# untitled.net
KiCad netlist of a schematic drawn in EAGLE
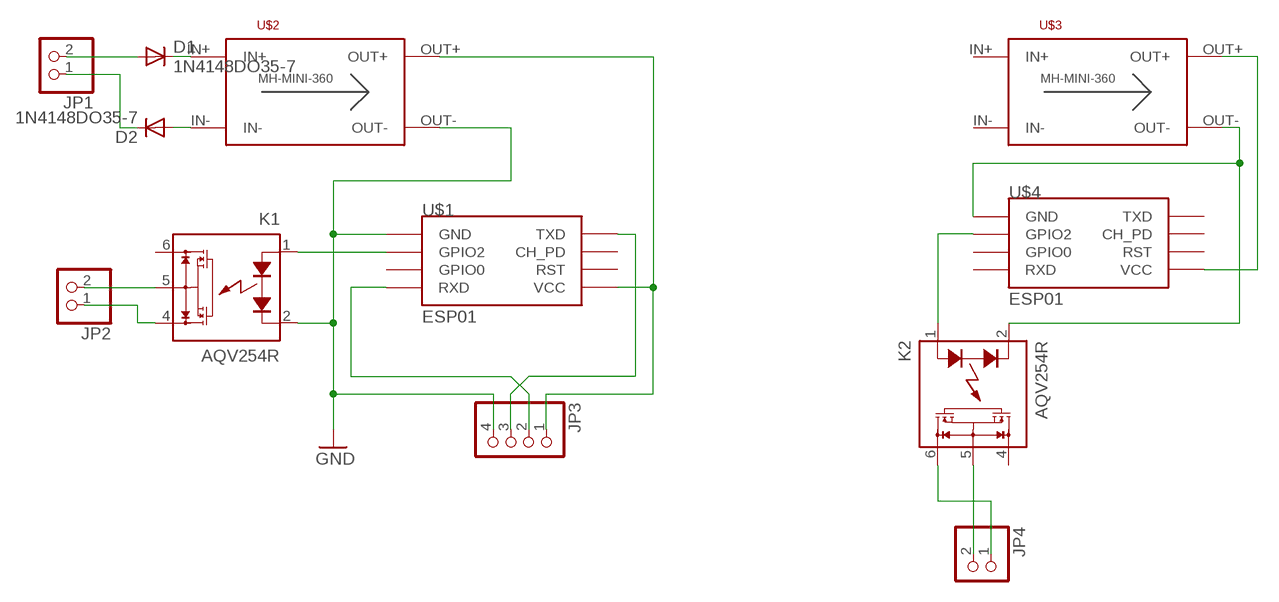
[diagram p0: schematic, sheet 1]

(export (version "E")
  (design (tool "Eeschema 10.0.6"))
  (components
    (comp (ref "D1")
      (value "1N4148DO35-7")
      (footprint "eagle-import:DO35-7")
      (libsource (lib "eagle-import") (part "1N4148DO35-7"))
    )
    (comp (ref "D2")
      (value "1N4148DO35-7")
      (footprint "eagle-import:DO35-7")
      (libsource (lib "eagle-import") (part "1N4148DO35-7"))
    )
    (comp (ref "JP1")
      (value "PINHD-1X2")
      (footprint "eagle-import:1X02")
      (libsource (lib "eagle-import") (part "PINHD-1X2"))
    )
    (comp (ref "JP2")
      (value "PINHD-1X2")
      (footprint "eagle-import:1X02")
      (libsource (lib "eagle-import") (part "PINHD-1X2"))
    )
    (comp (ref "JP3")
      (value "PINHD-1X4")
      (footprint "eagle-import:1X04")
      (libsource (lib "eagle-import") (part "PINHD-1X4"))
    )
    (comp (ref "JP4")
      (value "PINHD-1X2")
      (footprint "eagle-import:1X02")
      (libsource (lib "eagle-import") (part "PINHD-1X2"))
    )
    (comp (ref "K1")
      (value "AQV254R")
      (footprint "eagle-import:DIL06")
      (fields (field (name "MF") "AROMAT/ MATSUSHITA") (field (name "MPN") "AQV254"))
      (libsource (lib "eagle-import") (part "AQV254R"))
    )
    (comp (ref "K2")
      (value "AQV254R")
      (footprint "eagle-import:DIL06")
      (fields
        (field (name "MF") "AROMAT/ MATSUSHITA")
        (field (name "MPN") "AQV254")
        (field (name "MF_1") "AROMAT/ MATSUSHITA")
        (field (name "MPN_1") "AQV254")
        (field (name "OC_FARNELL") "1124063")
        (field (name "OC_NEWARK") "93F6300")
      )
      (libsource (lib "eagle-import") (part "AQV254R"))
    )
    (comp (ref "U$1")
      (value "ESP01")
      (footprint "eagle-import:ESP01")
      (libsource (lib "eagle-import") (part "ESP01"))
    )
    (comp (ref "U$2")
      (value "DC-DC_CONV_MINISTD")
      (footprint "eagle-import:DC-DC_CONV_MINI")
      (libsource (lib "eagle-import") (part "DC-DC_CONV_MINISTD"))
    )
    (comp (ref "U$3")
      (value "DC-DC_CONV_MINISTD")
      (footprint "eagle-import:DC-DC_CONV_MINI")
      (libsource (lib "eagle-import") (part "DC-DC_CONV_MINISTD"))
    )
    (comp (ref "U$4")
      (value "ESP01")
      (footprint "eagle-import:ESP01")
      (libsource (lib "eagle-import") (part "ESP01"))
    )
  )
  (nets
    (net (code "1") (name "GND") (class "Default")
      (node (ref "JP3") (pin "4") (pinfunction "4_4") (pintype "passive"))
      (node (ref "K1") (pin "2") (pinfunction "K_2") (pintype "passive"))
      (node (ref "U$1") (pin "GND") (pinfunction "GND_GND") (pintype "bidirectional"))
      (node (ref "U$2") (pin "OUT-") (pinfunction "OUT-_OUT-") (pintype "bidirectional"))
    )
    (net (code "2") (name "Net-(D1-PadA)") (class "Default")
      (node (ref "D1") (pin "A") (pinfunction "A_A") (pintype "passive"))
      (node (ref "JP1") (pin "2") (pinfunction "2_2") (pintype "passive"))
    )
    (net (code "3") (name "Net-(D1-PadC)") (class "Default")
      (node (ref "D1") (pin "C") (pinfunction "C_C") (pintype "passive"))
      (node (ref "U$2") (pin "IN+") (pinfunction "IN+_IN+") (pintype "bidirectional"))
    )
    (net (code "4") (name "Net-(D2-PadA)") (class "Default")
      (node (ref "D2") (pin "A") (pinfunction "A_A") (pintype "passive"))
      (node (ref "U$2") (pin "IN-") (pinfunction "IN-_IN-") (pintype "bidirectional"))
    )
    (net (code "5") (name "Net-(D2-PadC)") (class "Default")
      (node (ref "D2") (pin "C") (pinfunction "C_C") (pintype "passive"))
      (node (ref "JP1") (pin "1") (pinfunction "1_1") (pintype "passive"))
    )
    (net (code "6") (name "Net-(JP3-Pad1)") (class "Default")
      (node (ref "JP3") (pin "1") (pinfunction "1_1") (pintype "passive"))
      (node (ref "U$1") (pin "VCC") (pinfunction "VCC_VCC") (pintype "bidirectional"))
      (node (ref "U$2") (pin "OUT+") (pinfunction "OUT+_OUT+") (pintype "bidirectional"))
    )
    (net (code "7") (name "Net-(K1-A)") (class "Default")
      (node (ref "K1") (pin "1") (pinfunction "A_1") (pintype "passive"))
      (node (ref "U$1") (pin "GPIO2") (pinfunction "GPIO2_GPIO2") (pintype "bidirectional"))
    )
    (net (code "8") (name "Net-(K1-D2)") (class "Default")
      (node (ref "JP2") (pin "1") (pinfunction "1_1") (pintype "passive"))
      (node (ref "K1") (pin "4") (pinfunction "D2_4") (pintype "passive"))
    )
    (net (code "9") (name "Net-(K1-S)") (class "Default")
      (node (ref "JP2") (pin "2") (pinfunction "2_2") (pintype "passive"))
      (node (ref "K1") (pin "5") (pinfunction "S_5") (pintype "passive"))
    )
    (net (code "10") (name "Net-(K2-A)") (class "Default")
      (node (ref "K2") (pin "1") (pinfunction "A_1") (pintype "passive"))
      (node (ref "U$4") (pin "GPIO2") (pinfunction "GPIO2_GPIO2") (pintype "bidirectional"))
    )
    (net (code "11") (name "Net-(K2-D1)") (class "Default")
      (node (ref "JP4") (pin "1") (pinfunction "1_1") (pintype "passive"))
      (node (ref "K2") (pin "6") (pinfunction "D1_6") (pintype "passive"))
    )
    (net (code "12") (name "Net-(K2-K)") (class "Default")
      (node (ref "K2") (pin "2") (pinfunction "K_2") (pintype "passive"))
      (node (ref "U$3") (pin "OUT-") (pinfunction "OUT-_OUT-") (pintype "bidirectional"))
      (node (ref "U$4") (pin "GND") (pinfunction "GND_GND") (pintype "bidirectional"))
    )
    (net (code "13") (name "Net-(K2-S)") (class "Default")
      (node (ref "JP4") (pin "2") (pinfunction "2_2") (pintype "passive"))
      (node (ref "K2") (pin "5") (pinfunction "S_5") (pintype "passive"))
    )
    (net (code "14") (name "Net-(U$1-RXD)") (class "Default")
      (node (ref "JP3") (pin "2") (pinfunction "2_2") (pintype "passive"))
      (node (ref "U$1") (pin "RX") (pinfunction "RXD_RX") (pintype "bidirectional"))
    )
    (net (code "15") (name "Net-(U$1-TXD)") (class "Default")
      (node (ref "JP3") (pin "3") (pinfunction "3_3") (pintype "passive"))
      (node (ref "U$1") (pin "TX") (pinfunction "TXD_TX") (pintype "bidirectional"))
    )
    (net (code "16") (name "Net-(U$3-PadOUT+)") (class "Default")
      (node (ref "U$3") (pin "OUT+") (pinfunction "OUT+_OUT+") (pintype "bidirectional"))
      (node (ref "U$4") (pin "VCC") (pinfunction "VCC_VCC") (pintype "bidirectional"))
    )
    (net (code "17") (name "unconnected-(K1-D1-Pad6)") (class "Default")
      (node (ref "K1") (pin "6") (pinfunction "D1_6") (pintype "passive"))
    )
    (net (code "18") (name "unconnected-(K2-D2-Pad4)") (class "Default")
      (node (ref "K2") (pin "4") (pinfunction "D2_4") (pintype "passive"))
    )
    (net (code "19") (name "unconnected-(U$1-PadCH_PD)") (class "Default")
      (node (ref "U$1") (pin "CH_PD") (pinfunction "CH_PD_CH_PD") (pintype "bidirectional"))
    )
    (net (code "20") (name "unconnected-(U$1-PadGPIO0)") (class "Default")
      (node (ref "U$1") (pin "GPIO0") (pinfunction "GPIO0_GPIO0") (pintype "bidirectional"))
    )
    (net (code "21") (name "unconnected-(U$1-PadRST)") (class "Default")
      (node (ref "U$1") (pin "RST") (pinfunction "RST_RST") (pintype "bidirectional"))
    )
    (net (code "22") (name "unconnected-(U$3-PadIN+)") (class "Default")
      (node (ref "U$3") (pin "IN+") (pinfunction "IN+_IN+") (pintype "bidirectional"))
    )
    (net (code "23") (name "unconnected-(U$3-PadIN-)") (class "Default")
      (node (ref "U$3") (pin "IN-") (pinfunction "IN-_IN-") (pintype "bidirectional"))
    )
    (net (code "24") (name "unconnected-(U$4-PadCH_PD)") (class "Default")
      (node (ref "U$4") (pin "CH_PD") (pinfunction "CH_PD_CH_PD") (pintype "bidirectional"))
    )
    (net (code "25") (name "unconnected-(U$4-PadGPIO0)") (class "Default")
      (node (ref "U$4") (pin "GPIO0") (pinfunction "GPIO0_GPIO0") (pintype "bidirectional"))
    )
    (net (code "26") (name "unconnected-(U$4-PadRST)") (class "Default")
      (node (ref "U$4") (pin "RST") (pinfunction "RST_RST") (pintype "bidirectional"))
    )
    (net (code "27") (name "unconnected-(U$4-RXD-PadRX)") (class "Default")
      (node (ref "U$4") (pin "RX") (pinfunction "RXD_RX") (pintype "bidirectional"))
    )
    (net (code "28") (name "unconnected-(U$4-TXD-PadTX)") (class "Default")
      (node (ref "U$4") (pin "TX") (pinfunction "TXD_TX") (pintype "bidirectional"))
    )
  )
)
